# BrauV2_Buzzer.net
KiCad netlist of a schematic drawn in Altium Designer
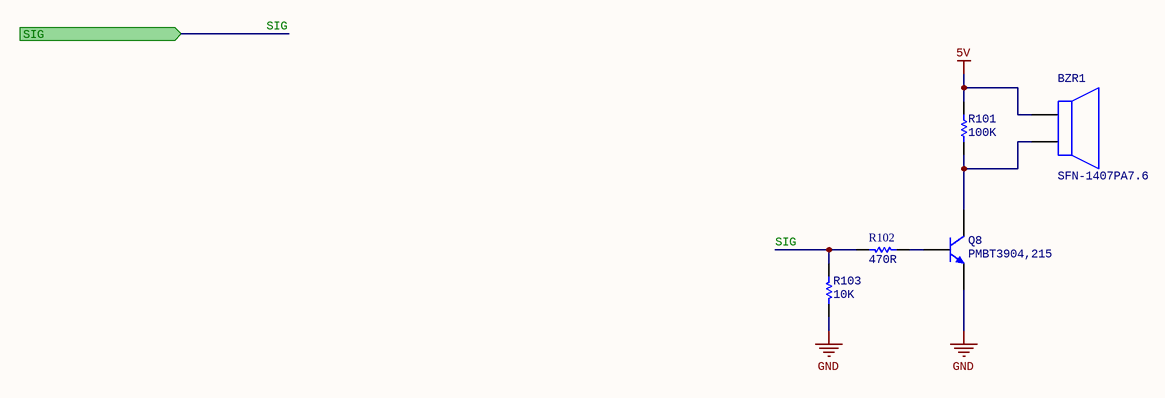
[diagram p0: BrauV2_Buzzer.SchDoc]

(export (version "E")
  (design (tool "Eeschema 10.0.6"))
  (components
    (comp (ref "BZR1")
      (value "SFN-1407PA7.6")
      (footprint "SFN-1407PA7.6")
      (description "Piezo YES 3300±500Hz 85dB @ 24V, 10cm 24V Φ23.5mm Through Hole Buzzers RoHS")
      (libsource (lib "BrauV2_Misc") (part "SFN-1407PA7.6"))
    )
    (comp (ref "Q8")
      (value "PMBT3904,215")
      (footprint "SOT23-3")
      (description "NPN 200mA 40V 250mW SOT-23(SOT-23-3) Transistors (NPN/PNP) RoHS")
      (libsource (lib "BrauV2_Transistor") (part "PMBT3904,215"))
    )
    (comp (ref "R101")
      (value "RC0402FR-07100KL")
      (footprint "SMD_RES_0402(1005)_N")
      (description "100kΩ ±1% 1/16W ±100ppm/℃ 0402 Chip Resistor - Surface Mount RoHS")
      (fields (field (name "TOLERANCE") "1%") (field (name "RESISTANCE") "100K"))
      (libsource (lib "BrauV2_Resistor") (part "100K 0402 1% 1/16W"))
    )
    (comp (ref "R102")
      (value "RC0402FR-07470RL")
      (footprint "SMD_RES_0402(1005)_N")
      (description "470Ω ±1% 1/16W ±100ppm/℃ 0402 Chip Resistor - Surface Mount RoHS")
      (fields (field (name "TOLERANCE") "1%") (field (name "RESISTANCE") "470R"))
      (libsource (lib "BrauV2_Resistor") (part "470R 0402 1% 1W"))
    )
    (comp (ref "R103")
      (value "RC0402FR-0710KL")
      (footprint "SMD_RES_0402(1005)_N")
      (description "10kΩ ±1% 1/16W ±100ppm/℃ 0402 Chip Resistor - Surface Mount RoHS")
      (fields (field (name "TOLERANCE") "1%") (field (name "RESISTANCE") "10K"))
      (libsource (lib "BrauV2_Resistor") (part "10K 0402 1% 1/16W"))
    )
  )
  (nets
    (net (code "1") (name "/SIG") (class "Default")
      (node (ref "R102") (pin "1") (pinfunction "1_1") (pintype "passive"))
      (node (ref "R103") (pin "2") (pinfunction "2_2") (pintype "passive"))
    )
    (net (code "2") (name "5V") (class "Default")
      (node (ref "BZR1") (pin "1") (pinfunction "1_1") (pintype "passive"))
      (node (ref "R101") (pin "2") (pinfunction "2_2") (pintype "passive"))
    )
    (net (code "3") (name "GND") (class "Default")
      (node (ref "Q8") (pin "2") (pinfunction "E_2") (pintype "passive"))
      (node (ref "R103") (pin "1") (pinfunction "1_1") (pintype "passive"))
    )
    (net (code "4") (name "Net-(Q8-B)") (class "Default")
      (node (ref "Q8") (pin "1") (pinfunction "B_1") (pintype "passive"))
      (node (ref "R102") (pin "2") (pinfunction "2_2") (pintype "passive"))
    )
    (net (code "5") (name "Net-(Q8-C)") (class "Default")
      (node (ref "BZR1") (pin "2") (pinfunction "2_2") (pintype "passive"))
      (node (ref "Q8") (pin "3") (pinfunction "C_3") (pintype "passive"))
      (node (ref "R101") (pin "1") (pinfunction "1_1") (pintype "passive"))
    )
  )
)
